# Analog_output.net
KiCad netlist of a schematic drawn in Altium Designer
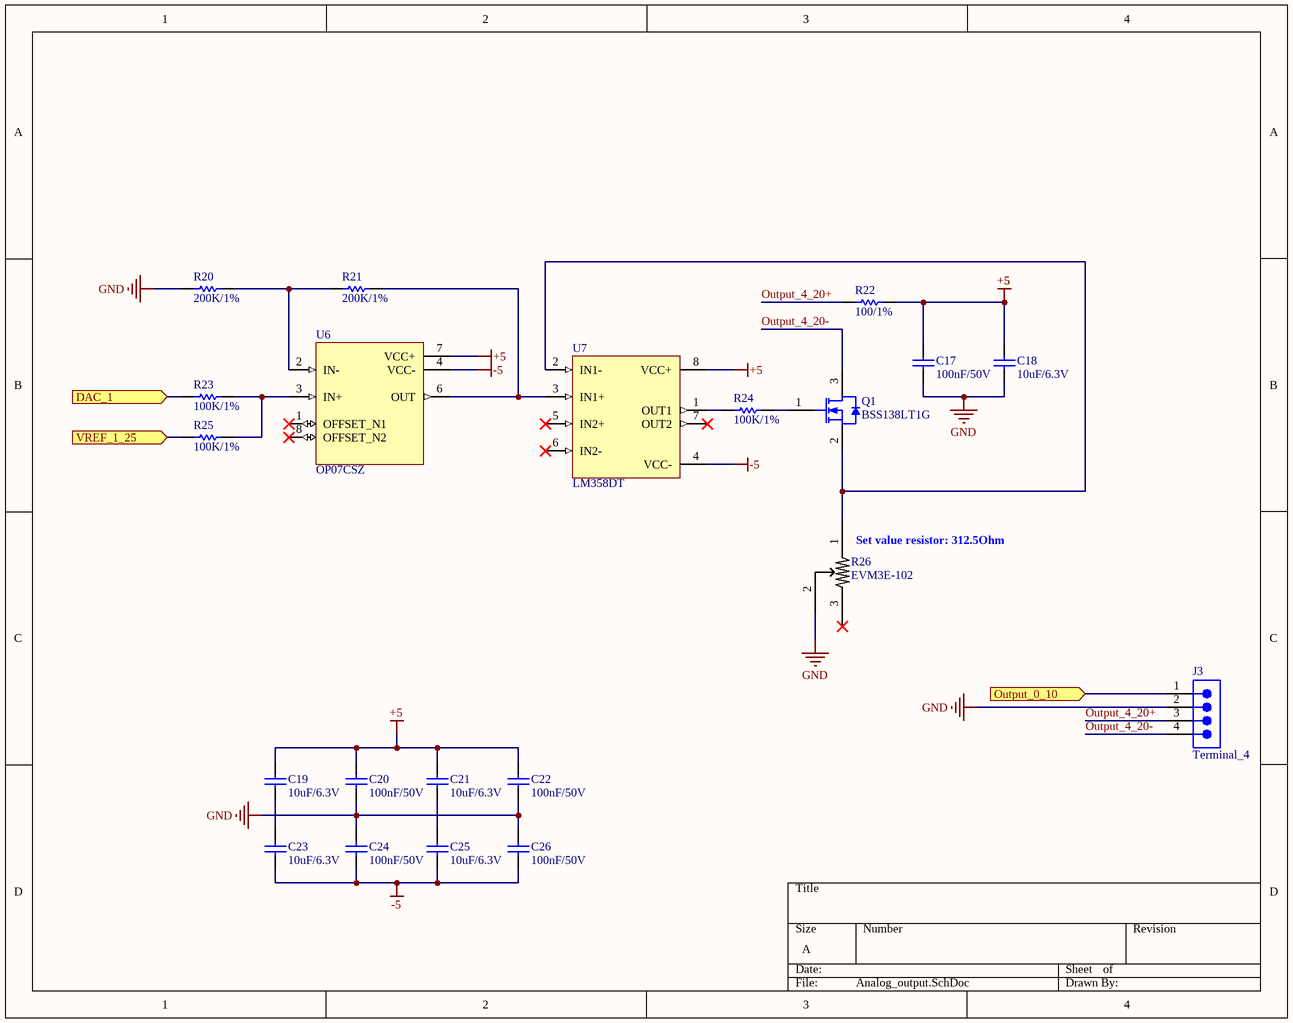
[diagram p0: Analog_output.SchDoc]

(export (version "E")
  (design (tool "Eeschema 10.0.6"))
  (components
    (comp (ref "C17")
      (value "100nF/50V")
      (footprint "CAP_0805")
      (libsource (lib "Iot_Flatform_lib_PTT") (part "Capacitor"))
    )
    (comp (ref "C18")
      (value "10uF/6.3V")
      (footprint "CAP_0805")
      (libsource (lib "Iot_Flatform_lib_PTT") (part "Capacitor"))
    )
    (comp (ref "C19")
      (value "10uF/6.3V")
      (footprint "CAP_0805")
      (libsource (lib "Iot_Flatform_lib_PTT") (part "Capacitor"))
    )
    (comp (ref "C20")
      (value "100nF/50V")
      (footprint "CAP_0805")
      (libsource (lib "Iot_Flatform_lib_PTT") (part "Capacitor"))
    )
    (comp (ref "C21")
      (value "10uF/6.3V")
      (footprint "CAP_0805")
      (libsource (lib "Iot_Flatform_lib_PTT") (part "Capacitor"))
    )
    (comp (ref "C22")
      (value "100nF/50V")
      (footprint "CAP_0805")
      (libsource (lib "Iot_Flatform_lib_PTT") (part "Capacitor"))
    )
    (comp (ref "C23")
      (value "10uF/6.3V")
      (footprint "CAP_0805")
      (libsource (lib "Iot_Flatform_lib_PTT") (part "Capacitor"))
    )
    (comp (ref "C24")
      (value "100nF/50V")
      (footprint "CAP_0805")
      (libsource (lib "Iot_Flatform_lib_PTT") (part "Capacitor"))
    )
    (comp (ref "C25")
      (value "10uF/6.3V")
      (footprint "CAP_0805")
      (libsource (lib "Iot_Flatform_lib_PTT") (part "Capacitor"))
    )
    (comp (ref "C26")
      (value "100nF/50V")
      (footprint "CAP_0805")
      (libsource (lib "Iot_Flatform_lib_PTT") (part "Capacitor"))
    )
    (comp (ref "J3")
      (value "Terminal_4")
      (footprint "TBL_4_3_81")
      (libsource (lib "Iot_Flatform_lib_PTT") (part "Terminal_4"))
    )
    (comp (ref "Q1")
      (value "BSS138LT1G")
      (footprint "SQ2398ES-SOT23")
      (description "BSS138LT1G, MOSFET, N ,50V, 200mA ,SOT-23")
      (libsource (lib "Iot_Flatform_lib_PTT") (part "BSS138LT1G"))
    )
    (comp (ref "R20")
      (value "200K/1%")
      (footprint "RES_0805")
      (libsource (lib "Iot_Flatform_lib_PTT") (part "Resistor"))
    )
    (comp (ref "R21")
      (value "200K/1%")
      (footprint "RES_0805")
      (libsource (lib "Iot_Flatform_lib_PTT") (part "Resistor"))
    )
    (comp (ref "R22")
      (value "100/1%")
      (footprint "RES_0805")
      (libsource (lib "Iot_Flatform_lib_PTT") (part "Resistor"))
    )
    (comp (ref "R23")
      (value "100K/1%")
      (footprint "RES_0805")
      (libsource (lib "Iot_Flatform_lib_PTT") (part "Resistor"))
    )
    (comp (ref "R24")
      (value "100K/1%")
      (footprint "RES_0805")
      (libsource (lib "Iot_Flatform_lib_PTT") (part "Resistor"))
    )
    (comp (ref "R25")
      (value "100K/1%")
      (footprint "RES_0805")
      (libsource (lib "Iot_Flatform_lib_PTT") (part "Resistor"))
    )
    (comp (ref "R26")
      (value "EVM3E-102")
      (footprint "EVM3E")
      (description "1KOhm, 0.15W,  ±20%, EVM3E")
      (libsource (lib "Iot_Flatform_lib_PTT") (part "EVM3E-102"))
    )
    (comp (ref "U6")
      (value "OP07CSZ")
      (footprint "SOIC127P600X175-8N")
      (description "Low-Offset Voltage Operational Amplifier")
      (libsource (lib "Iot_Flatform_lib_PTT") (part "OP07CSZ"))
    )
    (comp (ref "U7")
      (value "LM358DT")
      (footprint "SOIC127P600X175-8N")
      (description "General Purpose Amplifier 2 Circuit 8-SO")
      (libsource (lib "Iot_Flatform_lib_PTT") (part "LM358DT"))
    )
  )
  (nets
    (net (code "1") (name "+5") (class "Default")
      (node (ref "C17") (pin "2") (pinfunction "2_2") (pintype "passive"))
      (node (ref "C18") (pin "2") (pinfunction "2_2") (pintype "passive"))
      (node (ref "C19") (pin "2") (pinfunction "2_2") (pintype "passive"))
      (node (ref "C20") (pin "2") (pinfunction "2_2") (pintype "passive"))
      (node (ref "C21") (pin "2") (pinfunction "2_2") (pintype "passive"))
      (node (ref "C22") (pin "2") (pinfunction "2_2") (pintype "passive"))
      (node (ref "R22") (pin "2") (pinfunction "2_2") (pintype "passive"))
      (node (ref "U6") (pin "7") (pinfunction "VCC+_7") (pintype "power_in"))
      (node (ref "U7") (pin "8") (pinfunction "VCC+_8") (pintype "power_in"))
    )
    (net (code "2") (name "-5") (class "Default")
      (node (ref "C23") (pin "1") (pinfunction "1_1") (pintype "passive"))
      (node (ref "C24") (pin "1") (pinfunction "1_1") (pintype "passive"))
      (node (ref "C25") (pin "1") (pinfunction "1_1") (pintype "passive"))
      (node (ref "C26") (pin "1") (pinfunction "1_1") (pintype "passive"))
      (node (ref "U6") (pin "4") (pinfunction "VCC-_4") (pintype "power_in"))
      (node (ref "U7") (pin "4") (pinfunction "VCC-_4") (pintype "power_in"))
    )
    (net (code "3") (name "/DAC_1") (class "Default")
      (node (ref "R23") (pin "1") (pinfunction "1_1") (pintype "passive"))
    )
    (net (code "4") (name "/Output_0_10") (class "Default")
      (node (ref "J3") (pin "1") (pinfunction "1_1") (pintype "passive"))
    )
    (net (code "5") (name "/Output_4_20+") (class "Default")
      (node (ref "J3") (pin "3") (pinfunction "3_3") (pintype "passive"))
      (node (ref "R22") (pin "1") (pinfunction "1_1") (pintype "passive"))
    )
    (net (code "6") (name "/Output_4_20-") (class "Default")
      (node (ref "J3") (pin "4") (pinfunction "4_4") (pintype "passive"))
      (node (ref "Q1") (pin "3") (pinfunction "D_3") (pintype "passive"))
    )
    (net (code "7") (name "/VREF_1_25") (class "Default")
      (node (ref "R25") (pin "1") (pinfunction "1_1") (pintype "passive"))
    )
    (net (code "8") (name "GND") (class "Default")
      (node (ref "C17") (pin "1") (pinfunction "1_1") (pintype "passive"))
      (node (ref "C18") (pin "1") (pinfunction "1_1") (pintype "passive"))
      (node (ref "C20") (pin "1") (pinfunction "1_1") (pintype "passive"))
      (node (ref "C22") (pin "1") (pinfunction "1_1") (pintype "passive"))
      (node (ref "C24") (pin "2") (pinfunction "2_2") (pintype "passive"))
      (node (ref "C26") (pin "2") (pinfunction "2_2") (pintype "passive"))
      (node (ref "J3") (pin "2") (pinfunction "2_2") (pintype "passive"))
      (node (ref "R20") (pin "1") (pinfunction "1_1") (pintype "passive"))
      (node (ref "R26") (pin "2") (pinfunction "2_2") (pintype "passive"))
    )
    (net (code "9") (name "Net-(C19-Pad1)") (class "Default")
      (node (ref "C19") (pin "1") (pinfunction "1_1") (pintype "passive"))
      (node (ref "C23") (pin "2") (pinfunction "2_2") (pintype "passive"))
    )
    (net (code "10") (name "Net-(C21-Pad1)") (class "Default")
      (node (ref "C21") (pin "1") (pinfunction "1_1") (pintype "passive"))
      (node (ref "C25") (pin "2") (pinfunction "2_2") (pintype "passive"))
    )
    (net (code "11") (name "Net-(Q1-G)") (class "Default")
      (node (ref "Q1") (pin "1") (pinfunction "G_1") (pintype "passive"))
      (node (ref "R24") (pin "2") (pinfunction "2_2") (pintype "passive"))
    )
    (net (code "12") (name "Net-(Q1-S)") (class "Default")
      (node (ref "Q1") (pin "2") (pinfunction "S_2") (pintype "passive"))
      (node (ref "R26") (pin "1") (pinfunction "1_1") (pintype "passive"))
      (node (ref "U7") (pin "2") (pinfunction "IN1-_2") (pintype "input"))
    )
    (net (code "13") (name "Net-(U6-IN+)") (class "Default")
      (node (ref "R23") (pin "2") (pinfunction "2_2") (pintype "passive"))
      (node (ref "R25") (pin "2") (pinfunction "2_2") (pintype "passive"))
      (node (ref "U6") (pin "3") (pinfunction "IN+_3") (pintype "input"))
    )
    (net (code "14") (name "Net-(U6-IN-)") (class "Default")
      (node (ref "R20") (pin "2") (pinfunction "2_2") (pintype "passive"))
      (node (ref "R21") (pin "1") (pinfunction "1_1") (pintype "passive"))
      (node (ref "U6") (pin "2") (pinfunction "IN-_2") (pintype "input"))
    )
    (net (code "15") (name "Net-(U6-OUT)") (class "Default")
      (node (ref "R21") (pin "2") (pinfunction "2_2") (pintype "passive"))
      (node (ref "U6") (pin "6") (pinfunction "OUT_6") (pintype "output"))
      (node (ref "U7") (pin "3") (pinfunction "IN1+_3") (pintype "input"))
    )
    (net (code "16") (name "Net-(U7-OUT1)") (class "Default")
      (node (ref "R24") (pin "1") (pinfunction "1_1") (pintype "passive"))
      (node (ref "U7") (pin "1") (pinfunction "OUT1_1") (pintype "output"))
    )
    (net (code "17") (name "unconnected-(R26-Pad3)") (class "Default")
      (node (ref "R26") (pin "3") (pinfunction "3_3") (pintype "passive+no_connect"))
    )
    (net (code "18") (name "unconnected-(U6-OFFSET_N1-Pad1)") (class "Default")
      (node (ref "U6") (pin "1") (pinfunction "OFFSET_N1_1") (pintype "bidirectional+no_connect"))
    )
    (net (code "19") (name "unconnected-(U6-OFFSET_N2-Pad8)") (class "Default")
      (node (ref "U6") (pin "8") (pinfunction "OFFSET_N2_8") (pintype "bidirectional+no_connect"))
    )
    (net (code "20") (name "unconnected-(U7-IN2+-Pad5)") (class "Default")
      (node (ref "U7") (pin "5") (pinfunction "IN2+_5") (pintype "input+no_connect"))
    )
    (net (code "21") (name "unconnected-(U7-IN2--Pad6)") (class "Default")
      (node (ref "U7") (pin "6") (pinfunction "IN2-_6") (pintype "input+no_connect"))
    )
    (net (code "22") (name "unconnected-(U7-OUT2-Pad7)") (class "Default")
      (node (ref "U7") (pin "7") (pinfunction "OUT2_7") (pintype "output+no_connect"))
    )
  )
)
